# Extension_Board.net
KiCad netlist of a schematic drawn in Altium Designer
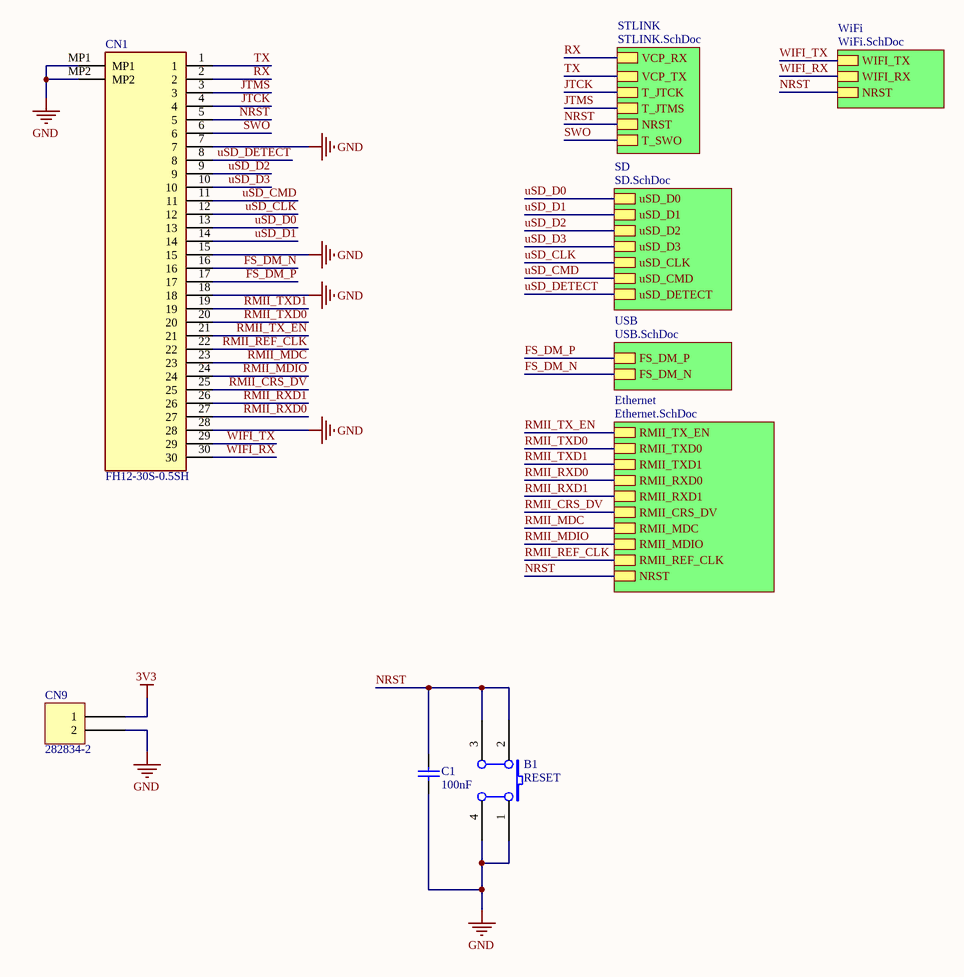
[diagram p0: Extension_Board.SchDoc]

(export (version "E")
  (design (tool "Eeschema 10.0.6"))
  (components
    (comp (ref "B1")
      (value "RESET")
      (footprint "PB-6X6mm-Blue")
      (description "SE PUSHBUTTON")
      (libsource (lib "MB1137") (part "SW PUSHBUTTON"))
    )
    (comp (ref "C1")
      (value "100nF")
      (footprint "1608[0603]")
      (description "Capacitor")
      (fields (field (name "Comment") "Cap") (field (name "PUBLISHER") "Altium Limited"))
      (libsource (lib "Miscellaneous Devices") (part "Cap"))
    )
    (comp (ref "CN1")
      (value "FH12-30S-0.5SH")
      (footprint "SamacSys:FH1230S05SH")
      (description "Connector")
      (libsource (lib "*") (part "FH12-30S-0.5SH"))
    )
    (comp (ref "CN9")
      (value "282834-2")
      (footprint "TE 282834-2")
      (description "TERM BLK 2P SIDE ENT 2.54MM PCB")
      (fields (field (name "MANUFACTURER") "TE Connectivity AMP Connectors") (field (name "VOLTAGE") "150V"))
      (libsource (lib "Celestial Altium Library - altium_library") (part "2 Pin"))
    )
  )
  (nets
    (net (code "1") (name "/FS_DM_N") (class "Default")
      (node (ref "CN1") (pin "16") (pinfunction "16_16") (pintype "passive"))
    )
    (net (code "2") (name "/FS_DM_P") (class "Default")
      (node (ref "CN1") (pin "17") (pinfunction "17_17") (pintype "passive"))
    )
    (net (code "3") (name "/JTCK") (class "Default")
      (node (ref "CN1") (pin "4") (pinfunction "4_4") (pintype "passive"))
    )
    (net (code "4") (name "/JTMS") (class "Default")
      (node (ref "CN1") (pin "3") (pinfunction "3_3") (pintype "passive"))
    )
    (net (code "5") (name "/NRST") (class "Default")
      (node (ref "B1") (pin "2") (pinfunction "B0_2") (pintype "passive"))
      (node (ref "B1") (pin "3") (pinfunction "B1_3") (pintype "passive"))
      (node (ref "C1") (pin "1") (pinfunction "1_1") (pintype "passive"))
      (node (ref "CN1") (pin "5") (pinfunction "5_5") (pintype "passive"))
    )
    (net (code "6") (name "/RMII_CRS_DV") (class "Default")
      (node (ref "CN1") (pin "25") (pinfunction "25_25") (pintype "passive"))
    )
    (net (code "7") (name "/RMII_MDC") (class "Default")
      (node (ref "CN1") (pin "23") (pinfunction "23_23") (pintype "passive"))
    )
    (net (code "8") (name "/RMII_MDIO") (class "Default")
      (node (ref "CN1") (pin "24") (pinfunction "24_24") (pintype "passive"))
    )
    (net (code "9") (name "/RMII_REF_CLK") (class "Default")
      (node (ref "CN1") (pin "22") (pinfunction "22_22") (pintype "passive"))
    )
    (net (code "10") (name "/RMII_RXD0") (class "Default")
      (node (ref "CN1") (pin "27") (pinfunction "27_27") (pintype "passive"))
    )
    (net (code "11") (name "/RMII_RXD1") (class "Default")
      (node (ref "CN1") (pin "26") (pinfunction "26_26") (pintype "passive"))
    )
    (net (code "12") (name "/RMII_TXD0") (class "Default")
      (node (ref "CN1") (pin "20") (pinfunction "20_20") (pintype "passive"))
    )
    (net (code "13") (name "/RMII_TXD1") (class "Default")
      (node (ref "CN1") (pin "19") (pinfunction "19_19") (pintype "passive"))
    )
    (net (code "14") (name "/RMII_TX_EN") (class "Default")
      (node (ref "CN1") (pin "21") (pinfunction "21_21") (pintype "passive"))
    )
    (net (code "15") (name "/RX") (class "Default")
      (node (ref "CN1") (pin "2") (pinfunction "2_2") (pintype "passive"))
    )
    (net (code "16") (name "/SWO") (class "Default")
      (node (ref "CN1") (pin "6") (pinfunction "6_6") (pintype "passive"))
    )
    (net (code "17") (name "/TX") (class "Default")
      (node (ref "CN1") (pin "1") (pinfunction "1_1") (pintype "passive"))
    )
    (net (code "18") (name "/WIFI_RX") (class "Default")
      (node (ref "CN1") (pin "30") (pinfunction "30_30") (pintype "passive"))
    )
    (net (code "19") (name "/WIFI_TX") (class "Default")
      (node (ref "CN1") (pin "29") (pinfunction "29_29") (pintype "passive"))
    )
    (net (code "20") (name "/uSD_CLK") (class "Default")
      (node (ref "CN1") (pin "12") (pinfunction "12_12") (pintype "passive"))
    )
    (net (code "21") (name "/uSD_CMD") (class "Default")
      (node (ref "CN1") (pin "11") (pinfunction "11_11") (pintype "passive"))
    )
    (net (code "22") (name "/uSD_D0") (class "Default")
      (node (ref "CN1") (pin "13") (pinfunction "13_13") (pintype "passive"))
    )
    (net (code "23") (name "/uSD_D1") (class "Default")
      (node (ref "CN1") (pin "14") (pinfunction "14_14") (pintype "passive"))
    )
    (net (code "24") (name "/uSD_D2") (class "Default")
      (node (ref "CN1") (pin "9") (pinfunction "9_9") (pintype "passive"))
    )
    (net (code "25") (name "/uSD_D3") (class "Default")
      (node (ref "CN1") (pin "10") (pinfunction "10_10") (pintype "passive"))
    )
    (net (code "26") (name "/uSD_DETECT") (class "Default")
      (node (ref "CN1") (pin "8") (pinfunction "8_8") (pintype "passive"))
    )
    (net (code "27") (name "3V3") (class "Default")
      (node (ref "CN9") (pin "1") (pinfunction "1_1") (pintype "passive"))
    )
    (net (code "28") (name "GND") (class "Default")
      (node (ref "B1") (pin "1") (pinfunction "A0_1") (pintype "passive"))
      (node (ref "B1") (pin "4") (pinfunction "A1_4") (pintype "passive"))
      (node (ref "C1") (pin "2") (pinfunction "2_2") (pintype "passive"))
      (node (ref "CN1") (pin "15") (pinfunction "15_15") (pintype "passive"))
      (node (ref "CN1") (pin "18") (pinfunction "18_18") (pintype "passive"))
      (node (ref "CN1") (pin "28") (pinfunction "28_28") (pintype "passive"))
      (node (ref "CN1") (pin "7") (pinfunction "7_7") (pintype "passive"))
      (node (ref "CN1") (pin "MP1") (pinfunction "MP1_MP1") (pintype "passive"))
      (node (ref "CN1") (pin "MP2") (pinfunction "MP2_MP2") (pintype "passive"))
      (node (ref "CN9") (pin "2") (pinfunction "2_2") (pintype "passive"))
    )
  )
)
